# Main_4000_Model.net
KiCad netlist of a schematic drawn in EAGLE
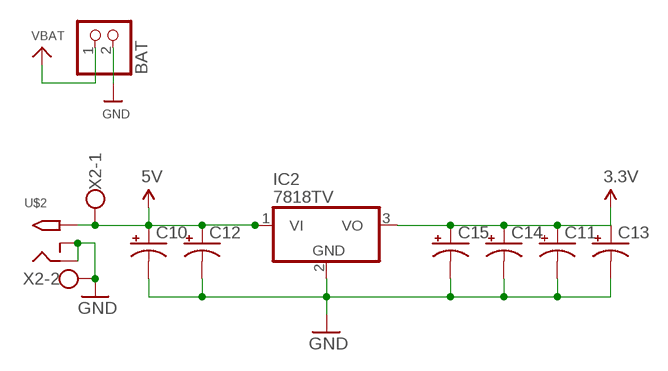
[diagram p0: schematic, sheet 1]
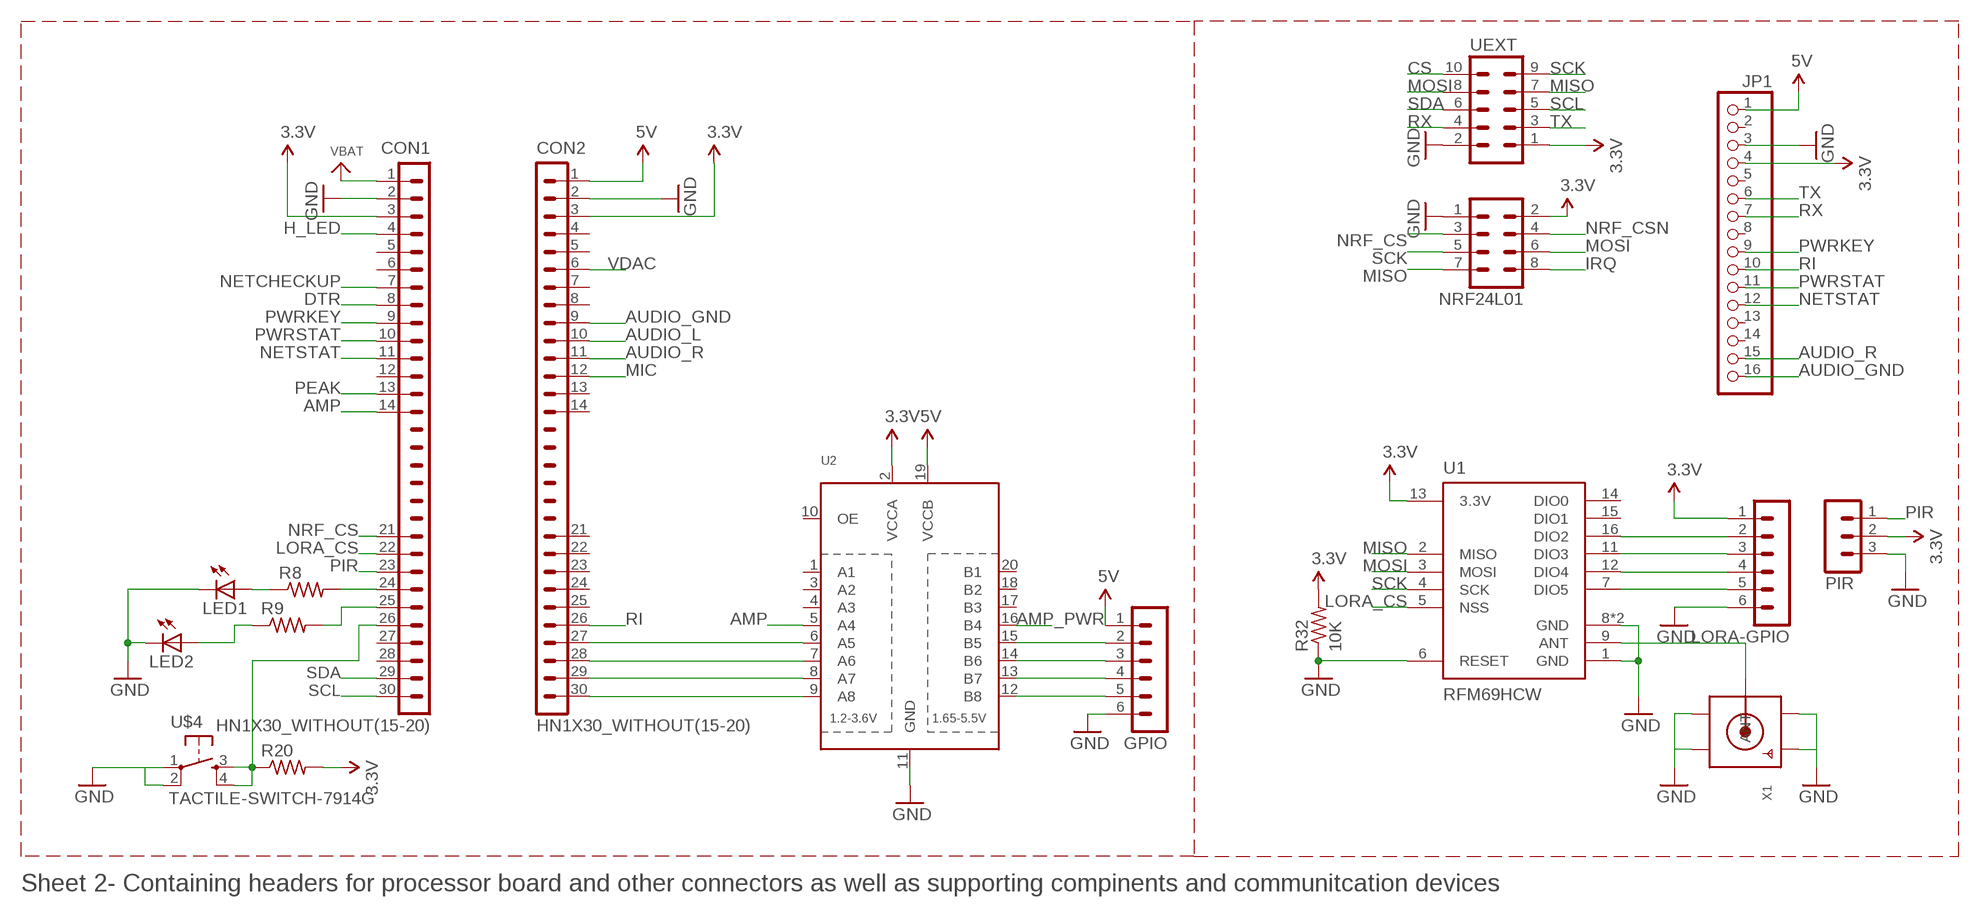
[diagram p1: schematic, sheet 2]
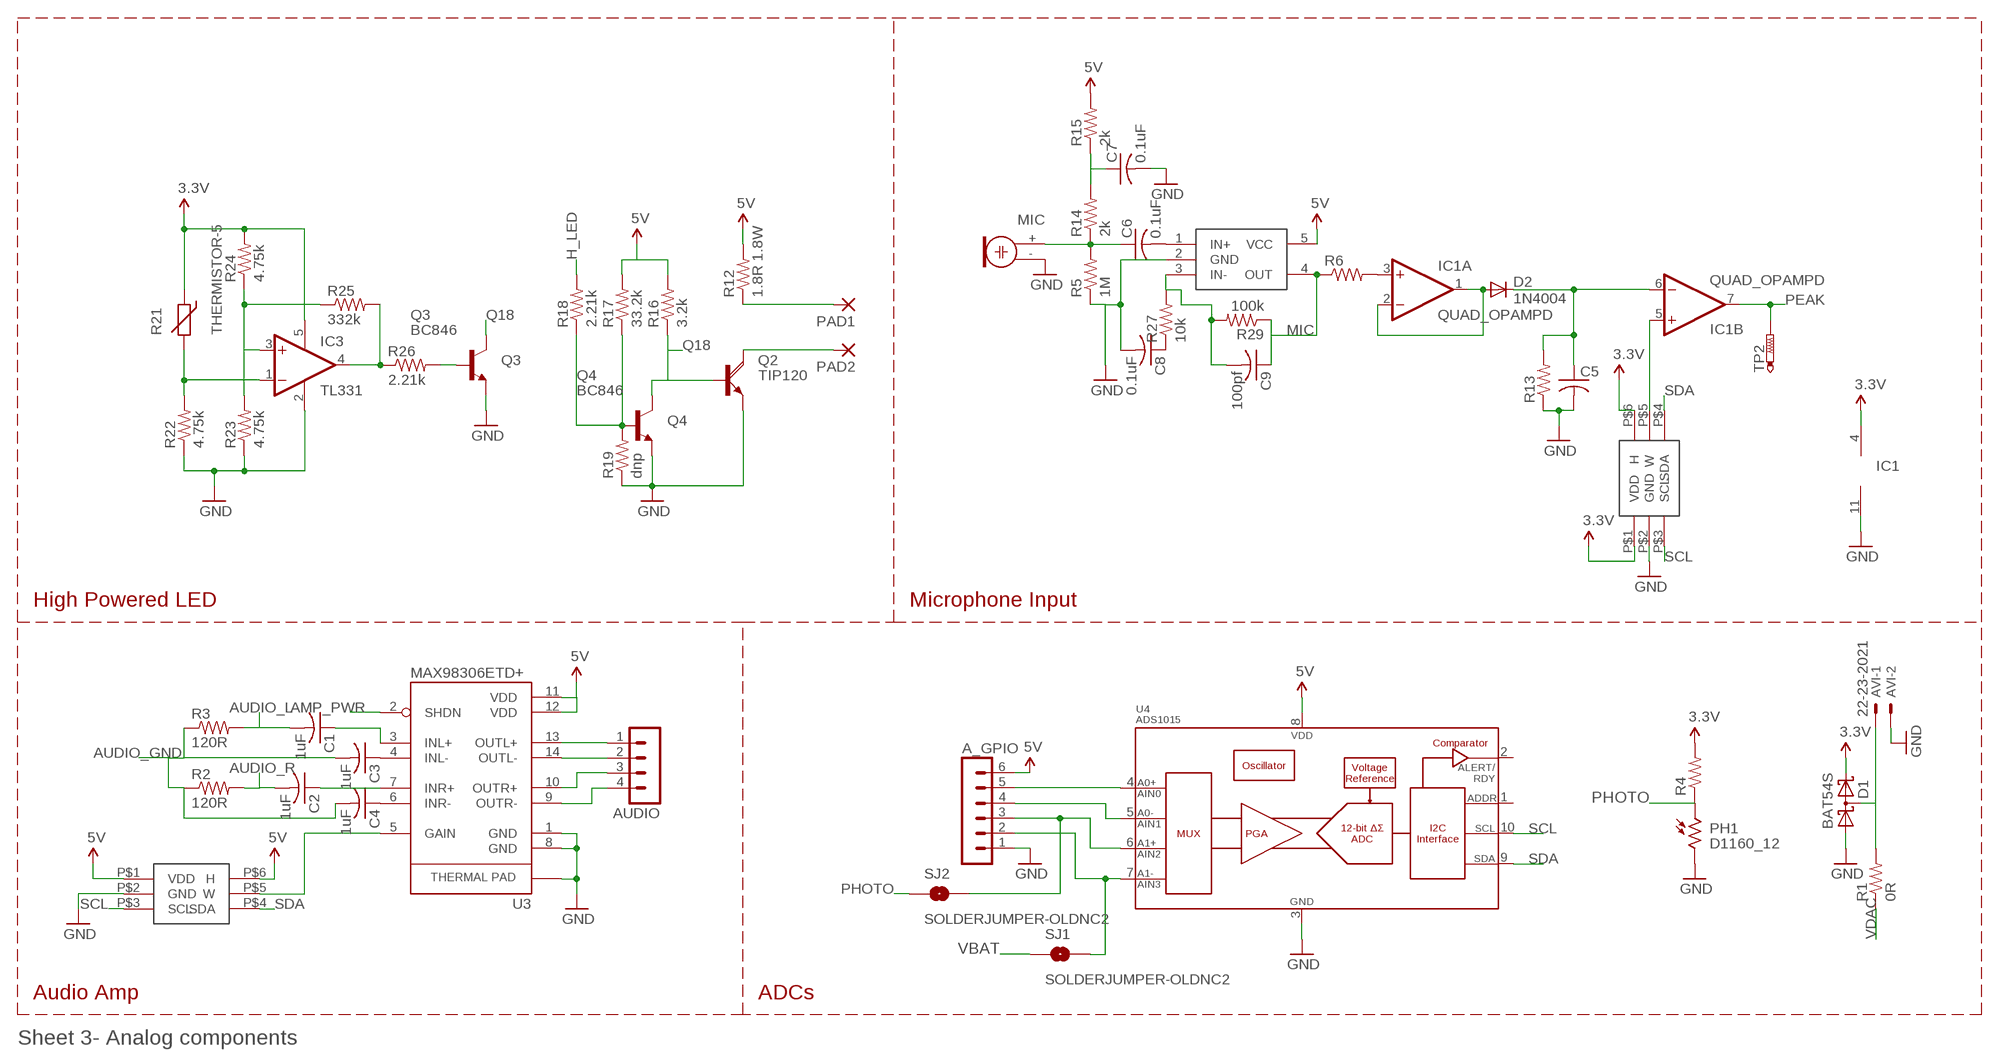
[diagram p2: schematic, sheet 3]
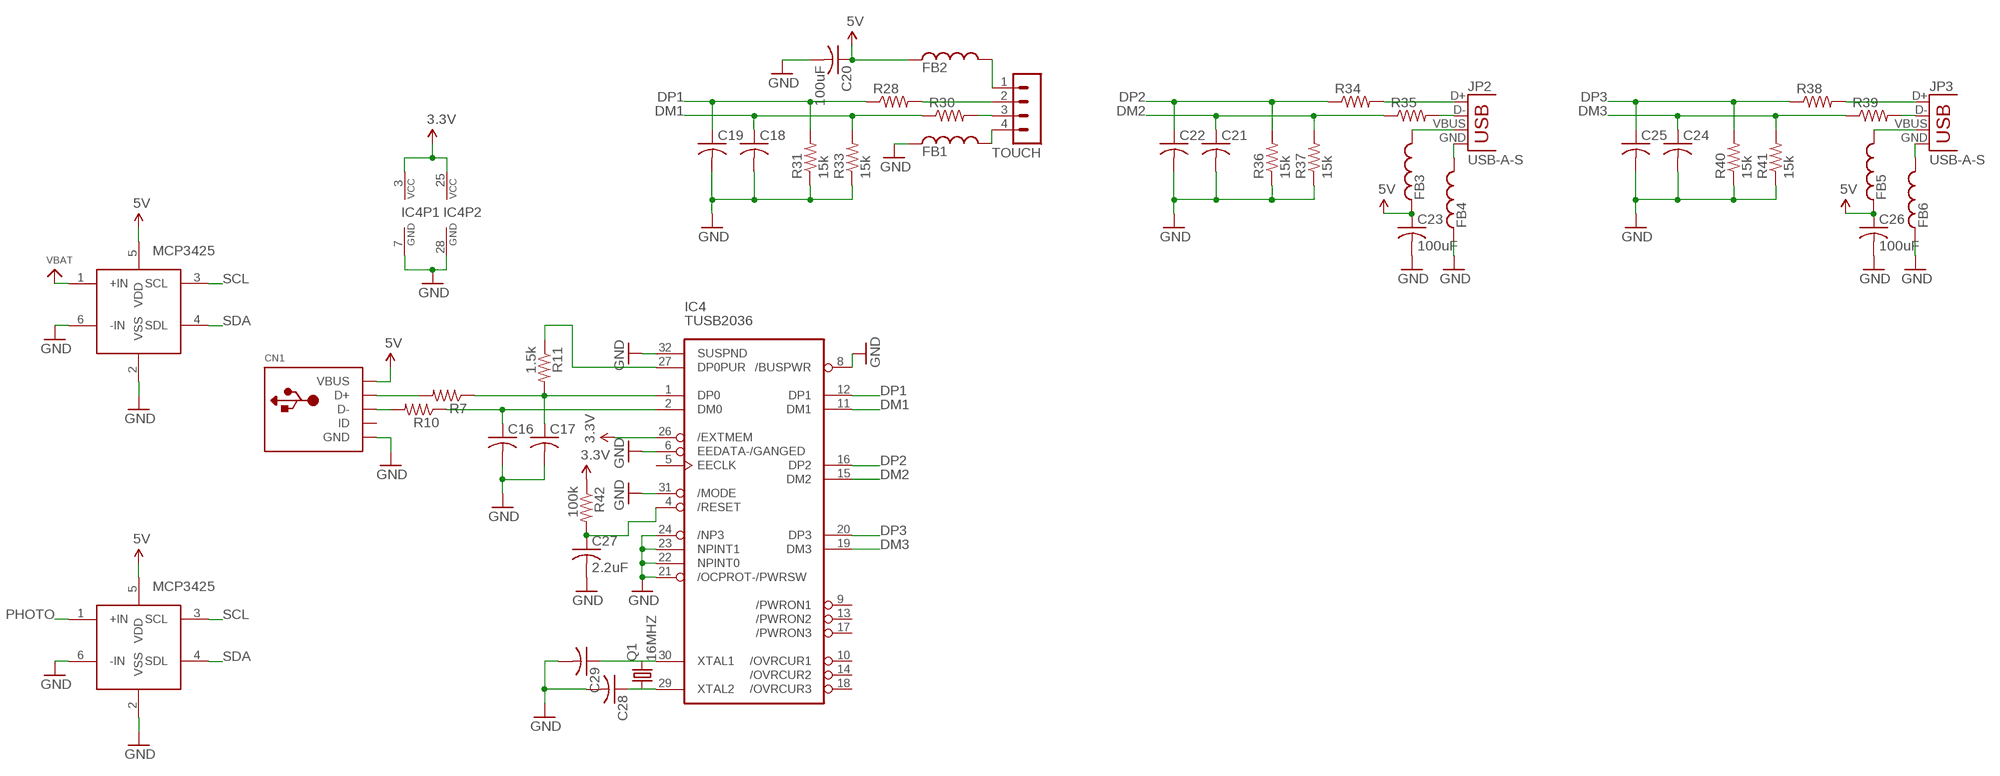
[diagram p3: schematic, sheet 4]

(export (version "E")
  (design (tool "Eeschema 10.0.6"))
  (components
    (comp (ref "CON1")
      (value "HN1X30_WITHOUT(15-20)")
      (footprint "eagle-import:HN1X30_WITHOUT(15-20)")
      (libsource (lib "eagle-import") (part "CON30_WITHOUT(15-20)"))
    )
    (comp (ref "CON2")
      (value "HN1X30_WITHOUT(15-20)")
      (footprint "eagle-import:HN1X30_WITHOUT(15-20)")
      (libsource (lib "eagle-import") (part "CON30_WITHOUT(15-20)"))
    )
    (comp (ref "GPIO")
      (value "MA06-1")
      (footprint "eagle-import:MA06-1")
      (libsource (lib "eagle-import") (part "MA06-1"))
    )
    (comp (ref "JP1")
      (value "PINHD-1X16")
      (footprint "eagle-import:1X16")
      (libsource (lib "eagle-import") (part "PINHD-1X16"))
    )
    (comp (ref "LED1")
      (value "LED5MM")
      (footprint "eagle-import:LED5MM")
      (libsource (lib "eagle-import") (part "LED5MM"))
    )
    (comp (ref "LED2")
      (value "LED5MM")
      (footprint "eagle-import:LED5MM")
      (libsource (lib "eagle-import") (part "LED5MM"))
    )
    (comp (ref "LORA-GPIO")
      (value "MA06-1")
      (footprint "eagle-import:MA06-1")
      (libsource (lib "eagle-import") (part "MA06-1"))
    )
    (comp (ref "NRF24L01")
      (value "MA04-2")
      (footprint "eagle-import:MA04-2")
      (libsource (lib "eagle-import") (part "MA04-2"))
    )
    (comp (ref "PIR")
      (value "MA03-1")
      (footprint "eagle-import:MA03-1")
      (libsource (lib "eagle-import") (part "MA03-1"))
    )
    (comp (ref "R8")
      (value "R-US_R0805")
      (footprint "eagle-import:R0805")
      (libsource (lib "eagle-import") (part "R-US_R0805"))
    )
    (comp (ref "R9")
      (value "R-US_R0805")
      (footprint "eagle-import:R0805")
      (libsource (lib "eagle-import") (part "R-US_R0805"))
    )
    (comp (ref "R20")
      (value "R-US_R0805")
      (footprint "eagle-import:R0805")
      (libsource (lib "eagle-import") (part "R-US_R0805"))
    )
    (comp (ref "R32")
      (value "10K")
      (footprint "eagle-import:R0805")
      (libsource (lib "eagle-import") (part "R-US_R0805"))
    )
    (comp (ref "U$4")
      (value "TACTILE-SWITCH-7914G")
      (footprint "eagle-import:7914G")
      (libsource (lib "eagle-import") (part "TACTILE-SWITCH-7914G"))
    )
    (comp (ref "U1")
      (value "RFM69HCW")
      (footprint "eagle-import:RFM69HCW-XXXS2")
      (libsource (lib "eagle-import") (part "RFM69HCW"))
    )
    (comp (ref "U2")
      (value "TXB0108PWR")
      (footprint "eagle-import:TSSOP20")
      (libsource (lib "eagle-import") (part "TXB0108PWR"))
    )
    (comp (ref "UEXT")
      (value "MA05-2")
      (footprint "eagle-import:MA05-2")
      (libsource (lib "eagle-import") (part "MA05-2"))
    )
    (comp (ref "X1")
      (value "SMACONNECTOR_EDGE")
      (footprint "eagle-import:SMA_EDGELAUNCH")
      (libsource (lib "eagle-import") (part "SMACONNECTOR_EDGE"))
    )
    (comp (ref "AUDIO")
      (value "MA04-1")
      (footprint "eagle-import:MA04-1")
      (libsource (lib "eagle-import") (part "MA04-1"))
    )
    (comp (ref "AVI")
      (value "22-23-2021")
      (footprint "eagle-import:22-23-2021")
      (fields (field (name "MF") "MOLEX"))
      (libsource (lib "eagle-import") (part "22-23-2021"))
    )
    (comp (ref "A_GPIO")
      (value "MA06-1")
      (footprint "eagle-import:MA06-1")
      (libsource (lib "eagle-import") (part "MA06-1"))
    )
    (comp (ref "C1")
      (value "1uF")
      (footprint "eagle-import:C0805")
      (libsource (lib "eagle-import") (part "C-USC0805"))
    )
    (comp (ref "C2")
      (value "1uF")
      (footprint "eagle-import:C0805")
      (libsource (lib "eagle-import") (part "C-USC0805"))
    )
    (comp (ref "C3")
      (value "1uF")
      (footprint "eagle-import:C0805")
      (libsource (lib "eagle-import") (part "C-USC0805"))
    )
    (comp (ref "C4")
      (value "1uF")
      (footprint "eagle-import:C0805")
      (libsource (lib "eagle-import") (part "C-USC0805"))
    )
    (comp (ref "C5")
      (value "C-USC0805K")
      (footprint "eagle-import:C0805K")
      (libsource (lib "eagle-import") (part "C-USC0805K"))
    )
    (comp (ref "C6")
      (value "0.1uF")
      (footprint "eagle-import:C0805")
      (libsource (lib "eagle-import") (part "C-USC0805"))
    )
    (comp (ref "C7")
      (value "0.1uF")
      (footprint "eagle-import:C0805")
      (libsource (lib "eagle-import") (part "C-USC0805"))
    )
    (comp (ref "C8")
      (value "0.1uF")
      (footprint "eagle-import:C0805")
      (libsource (lib "eagle-import") (part "C-USC0805"))
    )
    (comp (ref "C9")
      (value "100pf")
      (footprint "eagle-import:C0805")
      (libsource (lib "eagle-import") (part "C-USC0805"))
    )
    (comp (ref "D1")
      (value "BAT54S")
      (footprint "eagle-import:SOT23")
      (libsource (lib "eagle-import") (part "BAT54S"))
    )
    (comp (ref "D2")
      (value "1N4004")
      (footprint "eagle-import:DO41-10")
      (libsource (lib "eagle-import") (part "1N4004"))
    )
    (comp (ref "IC1")
      (value "QUAD_OPAMPD")
      (footprint "eagle-import:SO14")
      (libsource (lib "eagle-import") (part "QUAD_OPAMPD"))
    )
    (comp (ref "IC3")
      (value "TL331")
      (footprint "eagle-import:DBV-R-PDSO-G5")
      (libsource (lib "eagle-import") (part "TL331"))
    )
    (comp (ref "MIC")
      (value "ELECTRET")
      (footprint "eagle-import:9.7ELECTRET")
      (libsource (lib "eagle-import") (part "ELECTRET"))
    )
    (comp (ref "PAD1")
      (value "3,81/1,4")
      (footprint "eagle-import:3,81_1,4")
      (libsource (lib "eagle-import") (part "3,81/1,4"))
    )
    (comp (ref "PAD2")
      (value "3,81/1,4")
      (footprint "eagle-import:3,81_1,4")
      (libsource (lib "eagle-import") (part "3,81/1,4"))
    )
    (comp (ref "PH1")
      (value "D1160_12")
      (footprint "eagle-import:D11XX")
      (libsource (lib "eagle-import") (part "D1160_12"))
    )
    (comp (ref "Q2")
      (value "TIP120")
      (footprint "eagle-import:TO220AH")
      (libsource (lib "eagle-import") (part "TIP120"))
    )
    (comp (ref "Q3")
      (value "BC846")
      (footprint "eagle-import:SOT23")
      (libsource (lib "eagle-import") (part "BC846"))
    )
    (comp (ref "Q4")
      (value "BC846")
      (footprint "eagle-import:SOT23")
      (libsource (lib "eagle-import") (part "BC846"))
    )
    (comp (ref "R1")
      (value "0R")
      (footprint "eagle-import:R0805")
      (libsource (lib "eagle-import") (part "R-US_R0805"))
    )
    (comp (ref "R2")
      (value "120R")
      (footprint "eagle-import:R0805")
      (libsource (lib "eagle-import") (part "R-US_R0805"))
    )
    (comp (ref "R3")
      (value "120R")
      (footprint "eagle-import:R0805")
      (libsource (lib "eagle-import") (part "R-US_R0805"))
    )
    (comp (ref "R4")
      (value "R-US_R0805")
      (footprint "eagle-import:R0805")
      (libsource (lib "eagle-import") (part "R-US_R0805"))
    )
    (comp (ref "R5")
      (value "1M")
      (footprint "eagle-import:R0805")
      (libsource (lib "eagle-import") (part "R-US_R0805"))
    )
    (comp (ref "R6")
      (value "R-US_R0805")
      (footprint "eagle-import:R0805")
      (libsource (lib "eagle-import") (part "R-US_R0805"))
    )
    (comp (ref "R12")
      (value "1.8R 1.8W")
      (footprint "eagle-import:VMTB60")
      (libsource (lib "eagle-import") (part "R-US_VMTB60"))
    )
    (comp (ref "R13")
      (value "R-US_R0805")
      (footprint "eagle-import:R0805")
      (libsource (lib "eagle-import") (part "R-US_R0805"))
    )
    (comp (ref "R14")
      (value "2k")
      (footprint "eagle-import:R0805")
      (libsource (lib "eagle-import") (part "R-US_R0805"))
    )
    (comp (ref "R15")
      (value "2k")
      (footprint "eagle-import:R0805")
      (libsource (lib "eagle-import") (part "R-US_R0805"))
    )
    (comp (ref "R16")
      (value "3.2k")
      (footprint "eagle-import:R0805")
      (libsource (lib "eagle-import") (part "R-US_R0805"))
    )
    (comp (ref "R17")
      (value "33.2k")
      (footprint "eagle-import:R0805")
      (libsource (lib "eagle-import") (part "R-US_R0805"))
    )
    (comp (ref "R18")
      (value "2.21k")
      (footprint "eagle-import:R0805")
      (libsource (lib "eagle-import") (part "R-US_R0805"))
    )
    (comp (ref "R19")
      (value "dnp")
      (footprint "eagle-import:R0805")
      (libsource (lib "eagle-import") (part "R-US_R0805"))
    )
    (comp (ref "R21")
      (value "THERMISTOR-5")
      (footprint "eagle-import:R-5")
      (libsource (lib "eagle-import") (part "THERMISTOR-5"))
    )
    (comp (ref "R22")
      (value "4.75k")
      (footprint "eagle-import:R0805")
      (libsource (lib "eagle-import") (part "R-US_R0805"))
    )
    (comp (ref "R23")
      (value "4.75k")
      (footprint "eagle-import:R0805")
      (libsource (lib "eagle-import") (part "R-US_R0805"))
    )
    (comp (ref "R24")
      (value "4.75k")
      (footprint "eagle-import:R0805")
      (libsource (lib "eagle-import") (part "R-US_R0805"))
    )
    (comp (ref "R25")
      (value "332k")
      (footprint "eagle-import:R0805")
      (libsource (lib "eagle-import") (part "R-US_R0805"))
    )
    (comp (ref "R26")
      (value "2.21k")
      (footprint "eagle-import:R0805")
      (libsource (lib "eagle-import") (part "R-US_R0805"))
    )
    (comp (ref "R27")
      (value "10k")
      (footprint "eagle-import:R0805")
      (libsource (lib "eagle-import") (part "R-US_R0805"))
    )
    (comp (ref "R29")
      (value "100k")
      (footprint "eagle-import:R0805")
      (libsource (lib "eagle-import") (part "R-US_R0805"))
    )
    (comp (ref "SJ1")
      (value "SOLDERJUMPER-OLDNC2")
      (footprint "eagle-import:SJ_2S-NOTRACE")
      (libsource (lib "eagle-import") (part "SOLDERJUMPER-OLDNC2"))
    )
    (comp (ref "SJ2")
      (value "SOLDERJUMPER-OLDNC2")
      (footprint "eagle-import:SJ_2S-NOTRACE")
      (libsource (lib "eagle-import") (part "SOLDERJUMPER-OLDNC2"))
    )
    (comp (ref "TP2")
      (value "PTR1PAD1-13")
      (footprint "eagle-import:P1-13")
      (libsource (lib "eagle-import") (part "PTR1PAD1-13"))
    )
    (comp (ref "U$1")
      (value "TPL0401A/B")
      (footprint "eagle-import:SC-70")
      (libsource (lib "eagle-import") (part "TPL0401A/B"))
    )
    (comp (ref "U$3")
      (value "MAX4466")
      (footprint "eagle-import:SOT23-5L")
      (libsource (lib "eagle-import") (part "MAX4466"))
    )
    (comp (ref "U$5")
      (value "TPL0401A/B")
      (footprint "eagle-import:SC-70")
      (libsource (lib "eagle-import") (part "TPL0401A/B"))
    )
    (comp (ref "U3")
      (value "MAX98306ETD+")
      (footprint "eagle-import:14-TDFN")
      (libsource (lib "eagle-import") (part "MAX98306ETD+"))
    )
    (comp (ref "U4")
      (value "ADS1015")
      (footprint "eagle-import:MSOP10")
      (libsource (lib "eagle-import") (part "ADS1015"))
    )
    (comp (ref "C16")
      (value "C-USC0805")
      (footprint "eagle-import:C0805")
      (libsource (lib "eagle-import") (part "C-USC0805"))
    )
    (comp (ref "C17")
      (value "C-USC0805")
      (footprint "eagle-import:C0805")
      (libsource (lib "eagle-import") (part "C-USC0805"))
    )
    (comp (ref "C18")
      (value "C-USC0805")
      (footprint "eagle-import:C0805")
      (libsource (lib "eagle-import") (part "C-USC0805"))
    )
    (comp (ref "C19")
      (value "C-USC0805")
      (footprint "eagle-import:C0805")
      (libsource (lib "eagle-import") (part "C-USC0805"))
    )
    (comp (ref "C20")
      (value "100uF")
      (footprint "eagle-import:C0805")
      (libsource (lib "eagle-import") (part "C-USC0805"))
    )
    (comp (ref "C21")
      (value "C-USC0805")
      (footprint "eagle-import:C0805")
      (libsource (lib "eagle-import") (part "C-USC0805"))
    )
    (comp (ref "C22")
      (value "C-USC0805")
      (footprint "eagle-import:C0805")
      (libsource (lib "eagle-import") (part "C-USC0805"))
    )
    (comp (ref "C23")
      (value "100uF")
      (footprint "eagle-import:C0805")
      (libsource (lib "eagle-import") (part "C-USC0805"))
    )
    (comp (ref "C24")
      (value "C-USC0805")
      (footprint "eagle-import:C0805")
      (libsource (lib "eagle-import") (part "C-USC0805"))
    )
    (comp (ref "C25")
      (value "C-USC0805")
      (footprint "eagle-import:C0805")
      (libsource (lib "eagle-import") (part "C-USC0805"))
    )
    (comp (ref "C26")
      (value "100uF")
      (footprint "eagle-import:C0805")
      (libsource (lib "eagle-import") (part "C-USC0805"))
    )
    (comp (ref "C27")
      (value "2.2uF")
      (footprint "eagle-import:C0805")
      (libsource (lib "eagle-import") (part "C-USC0805"))
    )
    (comp (ref "C28")
      (value "C-USC0805")
      (footprint "eagle-import:C0805")
      (libsource (lib "eagle-import") (part "C-USC0805"))
    )
    (comp (ref "C29")
      (value "C-USC0805")
      (footprint "eagle-import:C0805")
      (libsource (lib "eagle-import") (part "C-USC0805"))
    )
    (comp (ref "CN1")
      (value "USBMOLEX")
      (footprint "eagle-import:USB-MINIB-THM-MOLEX")
      (libsource (lib "eagle-import") (part "USBMOLEX"))
    )
    (comp (ref "FB1")
      (value "FB1206")
      (footprint "eagle-import:FB1206")
      (libsource (lib "eagle-import") (part "FB1206"))
    )
    (comp (ref "FB2")
      (value "FB1206")
      (footprint "eagle-import:FB1206")
      (libsource (lib "eagle-import") (part "FB1206"))
    )
    (comp (ref "FB3")
      (value "FB1206")
      (footprint "eagle-import:FB1206")
      (libsource (lib "eagle-import") (part "FB1206"))
    )
    (comp (ref "FB4")
      (value "FB1206")
      (footprint "eagle-import:FB1206")
      (libsource (lib "eagle-import") (part "FB1206"))
    )
    (comp (ref "FB5")
      (value "FB1206")
      (footprint "eagle-import:FB1206")
      (libsource (lib "eagle-import") (part "FB1206"))
    )
    (comp (ref "FB6")
      (value "FB1206")
      (footprint "eagle-import:FB1206")
      (libsource (lib "eagle-import") (part "FB1206"))
    )
    (comp (ref "IC4")
      (value "TUSB2036")
      (footprint "eagle-import:LQFP32")
      (libsource (lib "eagle-import") (part "TUSB2036"))
    )
    (comp (ref "JP2")
      (value "USB-A-S")
      (footprint "eagle-import:USB-A-S")
      (libsource (lib "eagle-import") (part "USB-A-S"))
    )
    (comp (ref "JP3")
      (value "USB-A-S")
      (footprint "eagle-import:USB-A-S")
      (libsource (lib "eagle-import") (part "USB-A-S"))
    )
    (comp (ref "Q1")
      (value "16MHZ")
      (footprint "eagle-import:HC49UP")
      (libsource (lib "eagle-import") (part "CRYSTALHC49UP"))
    )
    (comp (ref "R7")
      (value "R-US_R0805")
      (footprint "eagle-import:R0805")
      (libsource (lib "eagle-import") (part "R-US_R0805"))
    )
    (comp (ref "R10")
      (value "R-US_R0805")
      (footprint "eagle-import:R0805")
      (libsource (lib "eagle-import") (part "R-US_R0805"))
    )
    (comp (ref "R11")
      (value "1.5k")
      (footprint "eagle-import:R0805")
      (libsource (lib "eagle-import") (part "R-US_R0805"))
    )
    (comp (ref "R28")
      (value "R-US_R0805")
      (footprint "eagle-import:R0805")
      (libsource (lib "eagle-import") (part "R-US_R0805"))
    )
    (comp (ref "R30")
      (value "R-US_R0805")
      (footprint "eagle-import:R0805")
      (libsource (lib "eagle-import") (part "R-US_R0805"))
    )
    (comp (ref "R31")
      (value "15k")
      (footprint "eagle-import:R0805")
      (libsource (lib "eagle-import") (part "R-US_R0805"))
    )
    (comp (ref "R33")
      (value "15k")
      (footprint "eagle-import:R0805")
      (libsource (lib "eagle-import") (part "R-US_R0805"))
    )
    (comp (ref "R34")
      (value "R-US_R0805")
      (footprint "eagle-import:R0805")
      (libsource (lib "eagle-import") (part "R-US_R0805"))
    )
    (comp (ref "R35")
      (value "R-US_R0805")
      (footprint "eagle-import:R0805")
      (libsource (lib "eagle-import") (part "R-US_R0805"))
    )
    (comp (ref "R36")
      (value "15k")
      (footprint "eagle-import:R0805")
      (libsource (lib "eagle-import") (part "R-US_R0805"))
    )
    (comp (ref "R37")
      (value "15k")
      (footprint "eagle-import:R0805")
      (libsource (lib "eagle-import") (part "R-US_R0805"))
    )
    (comp (ref "R38")
      (value "R-US_R0805")
      (footprint "eagle-import:R0805")
      (libsource (lib "eagle-import") (part "R-US_R0805"))
    )
    (comp (ref "R39")
      (value "R-US_R0805")
      (footprint "eagle-import:R0805")
      (libsource (lib "eagle-import") (part "R-US_R0805"))
    )
    (comp (ref "R40")
      (value "15k")
      (footprint "eagle-import:R0805")
      (libsource (lib "eagle-import") (part "R-US_R0805"))
    )
    (comp (ref "R41")
      (value "15k")
      (footprint "eagle-import:R0805")
      (libsource (lib "eagle-import") (part "R-US_R0805"))
    )
    (comp (ref "R42")
      (value "100k")
      (footprint "eagle-import:R0805")
      (libsource (lib "eagle-import") (part "R-US_R0805"))
    )
    (comp (ref "TOUCH")
      (value "MA04-1")
      (footprint "eagle-import:MA04-1")
      (libsource (lib "eagle-import") (part "MA04-1"))
    )
    (comp (ref "U$6")
      (value "MCP3425SOT")
      (footprint "eagle-import:SOT23-6")
      (libsource (lib "eagle-import") (part "MCP3425SOT"))
    )
    (comp (ref "U$8")
      (value "MCP3425SOT")
      (footprint "eagle-import:SOT23-6")
      (libsource (lib "eagle-import") (part "MCP3425SOT"))
    )
    (comp (ref "BAT")
      (value "JST_2PIN-SMT-RA")
      (footprint "eagle-import:JST-PH-2-SMT-RA")
      (libsource (lib "eagle-import") (part "JST_2PIN-SMT-RA"))
    )
    (comp (ref "C10")
      (value "CPOL-USE2.5-6")
      (footprint "eagle-import:E2,5-6")
      (libsource (lib "eagle-import") (part "CPOL-USE2.5-6"))
    )
    (comp (ref "C11")
      (value "CPOL-USE1.8-4")
      (footprint "eagle-import:E1,8-4")
      (libsource (lib "eagle-import") (part "CPOL-USE1.8-4"))
    )
    (comp (ref "C12")
      (value "CPOL-USE1.8-4")
      (footprint "eagle-import:E1,8-4")
      (libsource (lib "eagle-import") (part "CPOL-USE1.8-4"))
    )
    (comp (ref "C13")
      (value "CPOL-USE2.5-6")
      (footprint "eagle-import:E2,5-6")
      (libsource (lib "eagle-import") (part "CPOL-USE2.5-6"))
    )
    (comp (ref "C14")
      (value "CPOL-USE1.8-4")
      (footprint "eagle-import:E1,8-4")
      (libsource (lib "eagle-import") (part "CPOL-USE1.8-4"))
    )
    (comp (ref "C15")
      (value "CPOL-USE1.8-4")
      (footprint "eagle-import:E1,8-4")
      (libsource (lib "eagle-import") (part "CPOL-USE1.8-4"))
    )
    (comp (ref "IC2")
      (value "7818TV")
      (footprint "eagle-import:TO220V")
      (libsource (lib "eagle-import") (part "78TV18"))
    )
    (comp (ref "U$2")
      (value "2.1MMJACKTHM")
      (footprint "eagle-import:PJ-102A")
      (libsource (lib "eagle-import") (part "2.1MMJACKTHM"))
    )
    (comp (ref "X2")
      (value "W237-102")
      (footprint "eagle-import:W237-102")
      (fields (field (name "MPN") "237-102"))
      (libsource (lib "eagle-import") (part "W237-102"))
    )
  )
  (nets
    (net (code "1") (name "3.3V") (class "Default")
      (node (ref "C11") (pin "+") (pinfunction "+_+") (pintype "passive"))
      (node (ref "C13") (pin "+") (pinfunction "+_+") (pintype "passive"))
      (node (ref "C14") (pin "+") (pinfunction "+_+") (pintype "passive"))
      (node (ref "C15") (pin "+") (pinfunction "+_+") (pintype "passive"))
      (node (ref "CON1") (pin "3") (pinfunction "3_3") (pintype "passive"))
      (node (ref "CON2") (pin "3") (pinfunction "3_3") (pintype "passive"))
      (node (ref "D1") (pin "2") (pinfunction "C2_2") (pintype "passive"))
      (node (ref "IC1") (pin "4") (pinfunction "V+_4") (pintype "power_in"))
      (node (ref "IC2") (pin "3") (pinfunction "VO_3") (pintype "passive"))
      (node (ref "IC3") (pin "5") (pinfunction "V+_5") (pintype "power_in"))
      (node (ref "IC4") (pin "25") (pinfunction "VCC_25") (pintype "power_in"))
      (node (ref "IC4") (pin "26") (pinfunction "/EXTMEM_26") (pintype "input"))
      (node (ref "IC4") (pin "3") (pinfunction "VCC_3") (pintype "power_in"))
      (node (ref "JP1") (pin "4") (pinfunction "4_4") (pintype "passive"))
      (node (ref "LORA-GPIO") (pin "1") (pinfunction "1_1") (pintype "passive"))
      (node (ref "NRF24L01") (pin "2") (pinfunction "2_2") (pintype "passive"))
      (node (ref "PIR") (pin "2") (pinfunction "2_2") (pintype "passive"))
      (node (ref "R20") (pin "2") (pinfunction "2_2") (pintype "passive"))
      (node (ref "R21") (pin "1") (pinfunction "1_1") (pintype "passive"))
      (node (ref "R24") (pin "2") (pinfunction "2_2") (pintype "passive"))
      (node (ref "R32") (pin "2") (pinfunction "2_2") (pintype "passive"))
      (node (ref "R4") (pin "2") (pinfunction "2_2") (pintype "passive"))
      (node (ref "R42") (pin "1") (pinfunction "1_1") (pintype "passive"))
      (node (ref "U$5") (pin "P$1") (pinfunction "VDD_P$1") (pintype "bidirectional"))
      (node (ref "U$5") (pin "P$6") (pinfunction "H_P$6") (pintype "bidirectional"))
      (node (ref "U1") (pin "13") (pinfunction "3.3V_13") (pintype "power_in"))
      (node (ref "U2") (pin "2") (pinfunction "VCCA_2") (pintype "bidirectional"))
      (node (ref "UEXT") (pin "1") (pinfunction "1_1") (pintype "passive"))
    )
    (net (code "2") (name "5V") (class "Default")
      (node (ref "A_GPIO") (pin "6") (pinfunction "6_6") (pintype "passive"))
      (node (ref "C10") (pin "+") (pinfunction "+_+") (pintype "passive"))
      (node (ref "C12") (pin "+") (pinfunction "+_+") (pintype "passive"))
      (node (ref "C20") (pin "1") (pinfunction "1_1") (pintype "passive"))
      (node (ref "C23") (pin "1") (pinfunction "1_1") (pintype "passive"))
      (node (ref "C26") (pin "1") (pinfunction "1_1") (pintype "passive"))
      (node (ref "CN1") (pin "VBUS") (pinfunction "VBUS_VBUS") (pintype "power_in"))
      (node (ref "CON2") (pin "1") (pinfunction "1_1") (pintype "passive"))
      (node (ref "FB2") (pin "1") (pinfunction "1_1") (pintype "passive"))
      (node (ref "FB3") (pin "1") (pinfunction "1_1") (pintype "passive"))
      (node (ref "FB5") (pin "1") (pinfunction "1_1") (pintype "passive"))
      (node (ref "GPIO") (pin "1") (pinfunction "1_1") (pintype "passive"))
      (node (ref "IC2") (pin "1") (pinfunction "VI_1") (pintype "input"))
      (node (ref "JP1") (pin "1") (pinfunction "1_1") (pintype "passive"))
      (node (ref "R12") (pin "2") (pinfunction "2_2") (pintype "passive"))
      (node (ref "R15") (pin "2") (pinfunction "2_2") (pintype "passive"))
      (node (ref "R16") (pin "2") (pinfunction "2_2") (pintype "passive"))
      (node (ref "R17") (pin "2") (pinfunction "2_2") (pintype "passive"))
      (node (ref "U$1") (pin "P$1") (pinfunction "VDD_P$1") (pintype "bidirectional"))
      (node (ref "U$1") (pin "P$6") (pinfunction "H_P$6") (pintype "bidirectional"))
      (node (ref "U$2") (pin "TIP") (pinfunction "TIP_TIP") (pintype "bidirectional"))
      (node (ref "U$3") (pin "5") (pinfunction "VCC_5") (pintype "bidirectional"))
      (node (ref "U$6") (pin "5") (pinfunction "VDD_5") (pintype "bidirectional"))
      (node (ref "U$8") (pin "5") (pinfunction "VDD_5") (pintype "bidirectional"))
      (node (ref "U2") (pin "19") (pinfunction "VCCB_19") (pintype "bidirectional"))
      (node (ref "U3") (pin "11") (pinfunction "VDD_11") (pintype "power_in"))
      (node (ref "U3") (pin "12") (pinfunction "VDD_12") (pintype "power_in"))
      (node (ref "U4") (pin "8") (pinfunction "VDD_8") (pintype "bidirectional"))
      (node (ref "X2") (pin "1") (pinfunction "KL_1") (pintype "passive"))
    )
    (net (code "3") (name "AMP") (class "Default")
      (node (ref "CON1") (pin "14") (pinfunction "14_14") (pintype "passive"))
      (node (ref "U2") (pin "5") (pinfunction "A4_5") (pintype "bidirectional"))
    )
    (net (code "4") (name "AMP_PWR") (class "Default")
      (node (ref "U2") (pin "16") (pinfunction "B4_16") (pintype "bidirectional"))
      (node (ref "U3") (pin "2") (pinfunction "SHDN_2") (pintype "input"))
    )
    (net (code "5") (name "AUDIO_GND") (class "Default")
      (node (ref "C3") (pin "2") (pinfunction "2_2") (pintype "passive"))
      (node (ref "C4") (pin "2") (pinfunction "2_2") (pintype "passive"))
      (node (ref "CON2") (pin "9") (pinfunction "9_9") (pintype "passive"))
      (node (ref "JP1") (pin "16") (pinfunction "16_16") (pintype "passive"))
      (node (ref "R2") (pin "1") (pinfunction "1_1") (pintype "passive"))
      (node (ref "R3") (pin "1") (pinfunction "1_1") (pintype "passive"))
    )
    (net (code "6") (name "AUDIO_L") (class "Default")
      (node (ref "C1") (pin "2") (pinfunction "2_2") (pintype "passive"))
      (node (ref "CON2") (pin "10") (pinfunction "10_10") (pintype "passive"))
      (node (ref "R3") (pin "2") (pinfunction "2_2") (pintype "passive"))
    )
    (net (code "7") (name "AUDIO_R") (class "Default")
      (node (ref "C2") (pin "2") (pinfunction "2_2") (pintype "passive"))
      (node (ref "CON2") (pin "11") (pinfunction "11_11") (pintype "passive"))
      (node (ref "JP1") (pin "15") (pinfunction "15_15") (pintype "passive"))
      (node (ref "R2") (pin "2") (pinfunction "2_2") (pintype "passive"))
    )
    (net (code "8") (name "CS") (class "Default")
      (node (ref "UEXT") (pin "10") (pinfunction "10_10") (pintype "passive"))
    )
    (net (code "9") (name "DM1") (class "Default")
      (node (ref "C18") (pin "1") (pinfunction "1_1") (pintype "passive"))
      (node (ref "IC4") (pin "11") (pinfunction "DM1_11") (pintype "bidirectional"))
      (node (ref "R30") (pin "1") (pinfunction "1_1") (pintype "passive"))
      (node (ref "R33") (pin "2") (pinfunction "2_2") (pintype "passive"))
    )
    (net (code "10") (name "DM2") (class "Default")
      (node (ref "C21") (pin "1") (pinfunction "1_1") (pintype "passive"))
      (node (ref "IC4") (pin "15") (pinfunction "DM2_15") (pintype "bidirectional"))
      (node (ref "R35") (pin "1") (pinfunction "1_1") (pintype "passive"))
      (node (ref "R37") (pin "2") (pinfunction "2_2") (pintype "passive"))
    )
    (net (code "11") (name "DM3") (class "Default")
      (node (ref "C24") (pin "1") (pinfunction "1_1") (pintype "passive"))
      (node (ref "IC4") (pin "19") (pinfunction "DM3_19") (pintype "bidirectional"))
      (node (ref "R39") (pin "1") (pinfunction "1_1") (pintype "passive"))
      (node (ref "R41") (pin "2") (pinfunction "2_2") (pintype "passive"))
    )
    (net (code "12") (name "DP1") (class "Default")
      (node (ref "C19") (pin "1") (pinfunction "1_1") (pintype "passive"))
      (node (ref "IC4") (pin "12") (pinfunction "DP1_12") (pintype "bidirectional"))
      (node (ref "R28") (pin "1") (pinfunction "1_1") (pintype "passive"))
      (node (ref "R31") (pin "2") (pinfunction "2_2") (pintype "passive"))
    )
    (net (code "13") (name "DP2") (class "Default")
      (node (ref "C22") (pin "1") (pinfunction "1_1") (pintype "passive"))
      (node (ref "IC4") (pin "16") (pinfunction "DP2_16") (pintype "bidirectional"))
      (node (ref "R34") (pin "1") (pinfunction "1_1") (pintype "passive"))
      (node (ref "R36") (pin "2") (pinfunction "2_2") (pintype "passive"))
    )
    (net (code "14") (name "DP3") (class "Default")
      (node (ref "C25") (pin "1") (pinfunction "1_1") (pintype "passive"))
      (node (ref "IC4") (pin "20") (pinfunction "DP3_20") (pintype "bidirectional"))
      (node (ref "R38") (pin "1") (pinfunction "1_1") (pintype "passive"))
      (node (ref "R40") (pin "2") (pinfunction "2_2") (pintype "passive"))
    )
    (net (code "15") (name "DTR") (class "Default")
      (node (ref "CON1") (pin "8") (pinfunction "8_8") (pintype "passive"))
    )
    (net (code "16") (name "GND") (class "Default")
      (node (ref "AVI") (pin "2") (pinfunction "S_2") (pintype "passive"))
      (node (ref "A_GPIO") (pin "1") (pinfunction "1_1") (pintype "passive"))
      (node (ref "BAT") (pin "2") (pinfunction "1_2") (pintype "passive"))
      (node (ref "C10") (pin "-") (pinfunction "-_-") (pintype "passive"))
      (node (ref "C11") (pin "-") (pinfunction "-_-") (pintype "passive"))
      (node (ref "C12") (pin "-") (pinfunction "-_-") (pintype "passive"))
      (node (ref "C13") (pin "-") (pinfunction "-_-") (pintype "passive"))
      (node (ref "C14") (pin "-") (pinfunction "-_-") (pintype "passive"))
      (node (ref "C15") (pin "-") (pinfunction "-_-") (pintype "passive"))
      (node (ref "C16") (pin "2") (pinfunction "2_2") (pintype "passive"))
      (node (ref "C17") (pin "2") (pinfunction "2_2") (pintype "passive"))
      (node (ref "C18") (pin "2") (pinfunction "2_2") (pintype "passive"))
      (node (ref "C19") (pin "2") (pinfunction "2_2") (pintype "passive"))
      (node (ref "C20") (pin "2") (pinfunction "2_2") (pintype "passive"))
      (node (ref "C21") (pin "2") (pinfunction "2_2") (pintype "passive"))
      (node (ref "C22") (pin "2") (pinfunction "2_2") (pintype "passive"))
      (node (ref "C23") (pin "2") (pinfunction "2_2") (pintype "passive"))
      (node (ref "C24") (pin "2") (pinfunction "2_2") (pintype "passive"))
      (node (ref "C25") (pin "2") (pinfunction "2_2") (pintype "passive"))
      (node (ref "C26") (pin "2") (pinfunction "2_2") (pintype "passive"))
      (node (ref "C27") (pin "2") (pinfunction "2_2") (pintype "passive"))
      (node (ref "C28") (pin "2") (pinfunction "2_2") (pintype "passive"))
      (node (ref "C29") (pin "2") (pinfunction "2_2") (pintype "passive"))
      (node (ref "C5") (pin "2") (pinfunction "2_2") (pintype "passive"))
      (node (ref "C7") (pin "2") (pinfunction "2_2") (pintype "passive"))
      (node (ref "C8") (pin "2") (pinfunction "2_2") (pintype "passive"))
      (node (ref "CN1") (pin "GND") (pinfunction "GND_GND") (pintype "power_in"))
      (node (ref "CON1") (pin "2") (pinfunction "2_2") (pintype "passive"))
      (node (ref "CON2") (pin "2") (pinfunction "2_2") (pintype "passive"))
      (node (ref "D1") (pin "1") (pinfunction "A1_1") (pintype "passive"))
      (node (ref "FB1") (pin "1") (pinfunction "1_1") (pintype "passive"))
      (node (ref "FB4") (pin "1") (pinfunction "1_1") (pintype "passive"))
      (node (ref "FB6") (pin "1") (pinfunction "1_1") (pintype "passive"))
      (node (ref "GPIO") (pin "6") (pinfunction "6_6") (pintype "passive"))
      (node (ref "IC1") (pin "11") (pinfunction "V-_11") (pintype "power_in"))
      (node (ref "IC2") (pin "2") (pinfunction "GND_2") (pintype "passive"))
      (node (ref "IC3") (pin "2") (pinfunction "GND_2") (pintype "power_in"))
      (node (ref "IC4") (pin "21") (pinfunction "/OCPROT-/PWRSW_21") (pintype "input"))
      (node (ref "IC4") (pin "22") (pinfunction "NPINT0_22") (pintype "input"))
      (node (ref "IC4") (pin "23") (pinfunction "NPINT1_23") (pintype "input"))
      (node (ref "IC4") (pin "24") (pinfunction "/NP3_24") (pintype "input"))
      (node (ref "IC4") (pin "28") (pinfunction "GND_28") (pintype "power_in"))
      (node (ref "IC4") (pin "31") (pinfunction "/MODE_31") (pintype "input"))
      (node (ref "IC4") (pin "32") (pinfunction "SUSPND_32") (pintype "output"))
      (node (ref "IC4") (pin "6") (pinfunction "EEDATA-/GANGED_6") (pintype "bidirectional"))
      (node (ref "IC4") (pin "7") (pinfunction "GND_7") (pintype "power_in"))
      (node (ref "IC4") (pin "8") (pinfunction "/BUSPWR_8") (pintype "input"))
      (node (ref "JP1") (pin "3") (pinfunction "3_3") (pintype "passive"))
      (node (ref "LED1") (pin "K") (pinfunction "C_K") (pintype "passive"))
      (node (ref "LED2") (pin "K") (pinfunction "C_K") (pintype "passive"))
      (node (ref "LORA-GPIO") (pin "6") (pinfunction "6_6") (pintype "passive"))
      (node (ref "MIC") (pin "-") (pinfunction "1_-") (pintype "passive"))
      (node (ref "NRF24L01") (pin "1") (pinfunction "1_1") (pintype "passive"))
      (node (ref "PH1") (pin "2") (pinfunction "2_2") (pintype "passive"))
      (node (ref "PIR") (pin "3") (pinfunction "3_3") (pintype "passive"))
      (node (ref "Q2") (pin "E") (pinfunction "E_E") (pintype "passive"))
      (node (ref "Q3") (pin "2") (pinfunction "E_2") (pintype "passive"))
      (node (ref "Q4") (pin "2") (pinfunction "E_2") (pintype "passive"))
      (node (ref "R13") (pin "1") (pinfunction "1_1") (pintype "passive"))
      (node (ref "R19") (pin "1") (pinfunction "1_1") (pintype "passive"))
      (node (ref "R22") (pin "1") (pinfunction "1_1") (pintype "passive"))
      (node (ref "R23") (pin "1") (pinfunction "1_1") (pintype "passive"))
      (node (ref "R31") (pin "1") (pinfunction "1_1") (pintype "passive"))
      (node (ref "R32") (pin "1") (pinfunction "1_1") (pintype "passive"))
      (node (ref "R33") (pin "1") (pinfunction "1_1") (pintype "passive"))
      (node (ref "R36") (pin "1") (pinfunction "1_1") (pintype "passive"))
      (node (ref "R37") (pin "1") (pinfunction "1_1") (pintype "passive"))
      (node (ref "R40") (pin "1") (pinfunction "1_1") (pintype "passive"))
      (node (ref "R41") (pin "1") (pinfunction "1_1") (pintype "passive"))
      (node (ref "R5") (pin "1") (pinfunction "1_1") (pintype "passive"))
      (node (ref "U$1") (pin "P$2") (pinfunction "GND_P$2") (pintype "bidirectional"))
      (node (ref "U$2") (pin "RING") (pinfunction "RING_RING") (pintype "bidirectional"))
      (node (ref "U$2") (pin "RING_SW") (pinfunction "RING_SW_RING_SW") (pintype "bidirectional"))
      (node (ref "U$3") (pin "2") (pinfunction "GND_2") (pintype "bidirectional"))
      (node (ref "U$4") (pin "1") (pinfunction "1_1") (pintype "passive"))
      (node (ref "U$4") (pin "2") (pinfunction "2_2") (pintype "passive"))
      (node (ref "U$5") (pin "P$2") (pinfunction "GND_P$2") (pintype "bidirectional"))
      (node (ref "U$6") (pin "2") (pinfunction "VSS_2") (pintype "bidirectional"))
      (node (ref "U$6") (pin "6") (pinfunction "-IN_6") (pintype "bidirectional"))
      (node (ref "U$8") (pin "2") (pinfunction "VSS_2") (pintype "bidirectional"))
      (node (ref "U$8") (pin "6") (pinfunction "-IN_6") (pintype "bidirectional"))
      (node (ref "U1") (pin "1") (pinfunction "GND_1") (pintype "power_in"))
      (node (ref "U1") (pin "10") (pinfunction "GND_10") (pintype "power_in"))
      (node (ref "U1") (pin "6") (pinfunction "RESET_6") (pintype "input"))
      (node (ref "U1") (pin "8") (pinfunction "GND_8") (pintype "power_in"))
      (node (ref "U2") (pin "11") (pinfunction "GND_11") (pintype "bidirectional"))
      (node (ref "U3") (pin "1") (pinfunction "GND_1") (pintype "power_in"))
      (node (ref "U3") (pin "15") (pinfunction "GND_15") (pintype "power_in"))
      (node (ref "U3") (pin "8") (pinfunction "GND_8") (pintype "power_in"))
      (node (ref "U4") (pin "3") (pinfunction "VSS_3") (pintype "bidirectional"))
      (node (ref "UEXT") (pin "2") (pinfunction "2_2") (pintype "passive"))
      (node (ref "X1") (pin "GND@1") (pinfunction "GND4_GND@1") (pintype "power_in"))
      (node (ref "X1") (pin "GND@2") (pinfunction "GND3_GND@2") (pintype "power_in"))
      (node (ref "X1") (pin "GND@3") (pinfunction "GND2_GND@3") (pintype "power_in"))
      (node (ref "X1") (pin "GND@4") (pinfunction "GND1_GND@4") (pintype "power_in"))
      (node (ref "X2") (pin "2") (pinfunction "KL_2") (pintype "passive"))
    )
    (net (code "17") (name "H_LED") (class "Default")
      (node (ref "CON1") (pin "4") (pinfunction "4_4") (pintype "passive"))
      (node (ref "R18") (pin "2") (pinfunction "2_2") (pintype "passive"))
    )
    (net (code "18") (name "IRQ") (class "Default")
      (node (ref "NRF24L01") (pin "8") (pinfunction "8_8") (pintype "passive"))
    )
    (net (code "19") (name "LORA_CS") (class "Default")
      (node (ref "CON1") (pin "22") (pinfunction "22_22") (pintype "passive"))
      (node (ref "U1") (pin "5") (pinfunction "NSS_5") (pintype "input"))
    )
    (net (code "20") (name "MIC") (class "Default")
      (node (ref "C9") (pin "1") (pinfunction "1_1") (pintype "passive"))
      (node (ref "CON2") (pin "12") (pinfunction "12_12") (pintype "passive"))
      (node (ref "R29") (pin "1") (pinfunction "1_1") (pintype "passive"))
      (node (ref "R6") (pin "1") (pinfunction "1_1") (pintype "passive"))
      (node (ref "U$3") (pin "4") (pinfunction "OUT_4") (pintype "bidirectional"))
    )
    (net (code "21") (name "MISO") (class "Default")
      (node (ref "NRF24L01") (pin "7") (pinfunction "7_7") (pintype "passive"))
      (node (ref "U1") (pin "2") (pinfunction "MISO_2") (pintype "bidirectional"))
      (node (ref "UEXT") (pin "7") (pinfunction "7_7") (pintype "passive"))
    )
    (net (code "22") (name "MOSI") (class "Default")
      (node (ref "NRF24L01") (pin "6") (pinfunction "6_6") (pintype "passive"))
      (node (ref "U1") (pin "3") (pinfunction "MOSI_3") (pintype "input"))
      (node (ref "UEXT") (pin "8") (pinfunction "8_8") (pintype "passive"))
    )
    (net (code "23") (name "NETCHECKUP") (class "Default")
      (node (ref "CON1") (pin "7") (pinfunction "7_7") (pintype "passive"))
    )
    (net (code "24") (name "NETSTAT") (class "Default")
      (node (ref "CON1") (pin "11") (pinfunction "11_11") (pintype "passive"))
      (node (ref "JP1") (pin "12") (pinfunction "12_12") (pintype "passive"))
    )
    (net (code "25") (name "NRF_CS") (class "Default")
      (node (ref "CON1") (pin "21") (pinfunction "21_21") (pintype "passive"))
      (node (ref "NRF24L01") (pin "3") (pinfunction "3_3") (pintype "passive"))
    )
    (net (code "26") (name "NRF_CSN") (class "Default")
      (node (ref "NRF24L01") (pin "4") (pinfunction "4_4") (pintype "passive"))
    )
    (net (code "27") (name "Net-(AVIA-S)") (class "Default")
      (node (ref "AVI") (pin "1") (pinfunction "S_1") (pintype "passive"))
      (node (ref "D1") (pin "3") (pinfunction "C1A2_3") (pintype "passive"))
      (node (ref "R1") (pin "2") (pinfunction "2_2") (pintype "passive"))
    )
    (net (code "28") (name "Net-(C7-Pad1)") (class "Default")
      (node (ref "C7") (pin "1") (pinfunction "1_1") (pintype "passive"))
      (node (ref "R14") (pin "2") (pinfunction "2_2") (pintype "passive"))
      (node (ref "R15") (pin "1") (pinfunction "1_1") (pintype "passive"))
    )
    (net (code "29") (name "Net-(C8-Pad1)") (class "Default")
      (node (ref "C8") (pin "1") (pinfunction "1_1") (pintype "passive"))
      (node (ref "R27") (pin "1") (pinfunction "1_1") (pintype "passive"))
    )
    (net (code "30") (name "Net-(CN1-PadD+)") (class "Default")
      (node (ref "CN1") (pin "D+") (pinfunction "D+_D+") (pintype "bidirectional"))
      (node (ref "R7") (pin "2") (pinfunction "2_2") (pintype "passive"))
    )
    (net (code "31") (name "Net-(CN1-PadD-)") (class "Default")
      (node (ref "CN1") (pin "D-") (pinfunction "D-_D-") (pintype "bidirectional"))
      (node (ref "R10") (pin "2") (pinfunction "2_2") (pintype "passive"))
    )
    (net (code "32") (name "Net-(CON1-Pad24)") (class "Default")
      (node (ref "CON1") (pin "24") (pinfunction "24_24") (pintype "passive"))
      (node (ref "R8") (pin "2") (pinfunction "2_2") (pintype "passive"))
    )
    (net (code "33") (name "Net-(CON1-Pad25)") (class "Default")
      (node (ref "CON1") (pin "25") (pinfunction "25_25") (pintype "passive"))
      (node (ref "R9") (pin "2") (pinfunction "2_2") (pintype "passive"))
    )
    (net (code "34") (name "Net-(CON1-Pad26)") (class "Default")
      (node (ref "CON1") (pin "26") (pinfunction "26_26") (pintype "passive"))
      (node (ref "R20") (pin "1") (pinfunction "1_1") (pintype "passive"))
      (node (ref "U$4") (pin "3") (pinfunction "3_3") (pintype "passive"))
      (node (ref "U$4") (pin "4") (pinfunction "4_4") (pintype "passive"))
    )
    (net (code "35") (name "Net-(FB1-Pad2)") (class "Default")
      (node (ref "FB1") (pin "2") (pinfunction "2_2") (pintype "passive"))
      (node (ref "TOUCH") (pin "4") (pinfunction "4_4") (pintype "passive"))
    )
    (net (code "36") (name "Net-(FB2-Pad2)") (class "Default")
      (node (ref "FB2") (pin "2") (pinfunction "2_2") (pintype "passive"))
      (node (ref "TOUCH") (pin "1") (pinfunction "1_1") (pintype "passive"))
    )
    (net (code "37") (name "Net-(FB3-Pad2)") (class "Default")
      (node (ref "FB3") (pin "2") (pinfunction "2_2") (pintype "passive"))
      (node (ref "JP2") (pin "VBUS") (pinfunction "VBUS_VBUS") (pintype "bidirectional"))
    )
    (net (code "38") (name "Net-(FB4-Pad2)") (class "Default")
      (node (ref "FB4") (pin "2") (pinfunction "2_2") (pintype "passive"))
      (node (ref "JP2") (pin "GND") (pinfunction "GND_GND") (pintype "bidirectional"))
    )
    (net (code "39") (name "Net-(FB5-Pad2)") (class "Default")
      (node (ref "FB5") (pin "2") (pinfunction "2_2") (pintype "passive"))
      (node (ref "JP3") (pin "VBUS") (pinfunction "VBUS_VBUS") (pintype "bidirectional"))
    )
    (net (code "40") (name "Net-(FB6-Pad2)") (class "Default")
      (node (ref "FB6") (pin "2") (pinfunction "2_2") (pintype "passive"))
      (node (ref "JP3") (pin "GND") (pinfunction "GND_GND") (pintype "bidirectional"))
    )
    (net (code "41") (name "Net-(IC1A-+IN)") (class "Default")
      (node (ref "IC1") (pin "3") (pinfunction "+IN_3") (pintype "input"))
      (node (ref "R6") (pin "2") (pinfunction "2_2") (pintype "passive"))
    )
    (net (code "42") (name "Net-(IC1A--IN)") (class "Default")
      (node (ref "D2") (pin "A") (pinfunction "A_A") (pintype "passive"))
      (node (ref "IC1") (pin "1") (pinfunction "OUT_1") (pintype "output"))
      (node (ref "IC1") (pin "2") (pinfunction "-IN_2") (pintype "input"))
    )
    (net (code "43") (name "Net-(IC1B-+IN)") (class "Default")
      (node (ref "IC1") (pin "5") (pinfunction "+IN_5") (pintype "input"))
      (node (ref "U$5") (pin "P$5") (pinfunction "W_P$5") (pintype "bidirectional"))
    )
    (net (code "44") (name "Net-(IC1B--IN)") (class "Default")
      (node (ref "C5") (pin "1") (pinfunction "1_1") (pintype "passive"))
      (node (ref "D2") (pin "C") (pinfunction "C_C") (pintype "passive"))
      (node (ref "IC1") (pin "6") (pinfunction "-IN_6") (pintype "input"))
      (node (ref "R13") (pin "2") (pinfunction "2_2") (pintype "passive"))
    )
    (net (code "45") (name "Net-(IC3-+IN)") (class "Default")
      (node (ref "IC3") (pin "3") (pinfunction "+IN_3") (pintype "input"))
      (node (ref "R23") (pin "2") (pinfunction "2_2") (pintype "passive"))
      (node (ref "R24") (pin "1") (pinfunction "1_1") (pintype "passive"))
      (node (ref "R25") (pin "1") (pinfunction "1_1") (pintype "passive"))
    )
    (net (code "46") (name "Net-(IC3--IN)") (class "Default")
      (node (ref "IC3") (pin "1") (pinfunction "-IN_1") (pintype "input"))
      (node (ref "R21") (pin "2") (pinfunction "2_2") (pintype "passive"))
      (node (ref "R22") (pin "2") (pinfunction "2_2") (pintype "passive"))
    )
    (net (code "47") (name "Net-(IC3-OUT)") (class "Default")
      (node (ref "IC3") (pin "4") (pinfunction "OUT_4") (pintype "output"))
      (node (ref "R25") (pin "2") (pinfunction "2_2") (pintype "passive"))
      (node (ref "R26") (pin "1") (pinfunction "1_1") (pintype "passive"))
    )
    (net (code "48") (name "Net-(IC4A-DM0)") (class "Default")
      (node (ref "C16") (pin "1") (pinfunction "1_1") (pintype "passive"))
      (node (ref "IC4") (pin "2") (pinfunction "DM0_2") (pintype "bidirectional"))
      (node (ref "R10") (pin "1") (pinfunction "1_1") (pintype "passive"))
    )
    (net (code "49") (name "Net-(IC4A-DP0)") (class "Default")
      (node (ref "C17") (pin "1") (pinfunction "1_1") (pintype "passive"))
      (node (ref "IC4") (pin "1") (pinfunction "DP0_1") (pintype "bidirectional"))
      (node (ref "R11") (pin "2") (pinfunction "2_2") (pintype "passive"))
      (node (ref "R7") (pin "1") (pinfunction "1_1") (pintype "passive"))
    )
    (net (code "50") (name "Net-(IC4A-DP0PUR)") (class "Default")
      (node (ref "IC4") (pin "27") (pinfunction "DP0PUR_27") (pintype "output"))
      (node (ref "R11") (pin "1") (pinfunction "1_1") (pintype "passive"))
    )
    (net (code "51") (name "Net-(IC4A-XTAL1)") (class "Default")
      (node (ref "C29") (pin "1") (pinfunction "1_1") (pintype "passive"))
      (node (ref "IC4") (pin "30") (pinfunction "XTAL1_30") (pintype "input"))
      (node (ref "Q1") (pin "2") (pinfunction "2_2") (pintype "passive"))
    )
    (net (code "52") (name "Net-(IC4A-XTAL2)") (class "Default")
      (node (ref "C28") (pin "1") (pinfunction "1_1") (pintype "passive"))
      (node (ref "IC4") (pin "29") (pinfunction "XTAL2_29") (pintype "output"))
      (node (ref "Q1") (pin "1") (pinfunction "1_1") (pintype "passive"))
    )
    (net (code "53") (name "Net-(IC4A-{slash}RESET)") (class "Default")
      (node (ref "C27") (pin "1") (pinfunction "1_1") (pintype "passive"))
      (node (ref "IC4") (pin "4") (pinfunction "/RESET_4") (pintype "input"))
      (node (ref "R42") (pin "2") (pinfunction "2_2") (pintype "passive"))
    )
    (net (code "54") (name "Net-(JP2-PadD+)") (class "Default")
      (node (ref "JP2") (pin "D+") (pinfunction "D+_D+") (pintype "bidirectional"))
      (node (ref "R34") (pin "2") (pinfunction "2_2") (pintype "passive"))
    )
    (net (code "55") (name "Net-(JP2-PadD-)") (class "Default")
      (node (ref "JP2") (pin "D-") (pinfunction "D-_D-") (pintype "bidirectional"))
      (node (ref "R35") (pin "2") (pinfunction "2_2") (pintype "passive"))
    )
    (net (code "56") (name "Net-(JP3-PadD+)") (class "Default")
      (node (ref "JP3") (pin "D+") (pinfunction "D+_D+") (pintype "bidirectional"))
      (node (ref "R38") (pin "2") (pinfunction "2_2") (pintype "passive"))
    )
    (net (code "57") (name "Net-(JP3-PadD-)") (class "Default")
      (node (ref "JP3") (pin "D-") (pinfunction "D-_D-") (pintype "bidirectional"))
      (node (ref "R39") (pin "2") (pinfunction "2_2") (pintype "passive"))
    )
    (net (code "58") (name "Net-(LED1-PadA)") (class "Default")
      (node (ref "LED1") (pin "A") (pinfunction "A_A") (pintype "passive"))
      (node (ref "R8") (pin "1") (pinfunction "1_1") (pintype "passive"))
    )
    (net (code "59") (name "Net-(LED2-PadA)") (class "Default")
      (node (ref "LED2") (pin "A") (pinfunction "A_A") (pintype "passive"))
      (node (ref "R9") (pin "1") (pinfunction "1_1") (pintype "passive"))
    )
    (net (code "60") (name "Net-(MIC-2)") (class "Default")
      (node (ref "C6") (pin "1") (pinfunction "1_1") (pintype "passive"))
      (node (ref "MIC") (pin "+") (pinfunction "2_+") (pintype "passive"))
      (node (ref "R14") (pin "1") (pinfunction "1_1") (pintype "passive"))
      (node (ref "R5") (pin "2") (pinfunction "2_2") (pintype "passive"))
    )
    (net (code "61") (name "Net-(PAD1-P)") (class "Default")
      (node (ref "PAD1") (pin "1") (pinfunction "P_1") (pintype "passive"))
      (node (ref "R12") (pin "1") (pinfunction "1_1") (pintype "passive"))
    )
    (net (code "62") (name "Net-(PAD2-P)") (class "Default")
      (node (ref "PAD2") (pin "1") (pinfunction "P_1") (pintype "passive"))
      (node (ref "Q2") (pin "C") (pinfunction "C_C") (pintype "passive"))
    )
    (net (code "63") (name "Net-(Q3-B)") (class "Default")
      (node (ref "Q3") (pin "1") (pinfunction "B_1") (pintype "passive"))
      (node (ref "R26") (pin "2") (pinfunction "2_2") (pintype "passive"))
    )
    (net (code "64") (name "Net-(Q4-B)") (class "Default")
      (node (ref "Q4") (pin "1") (pinfunction "B_1") (pintype "passive"))
      (node (ref "R17") (pin "1") (pinfunction "1_1") (pintype "passive"))
      (node (ref "R18") (pin "1") (pinfunction "1_1") (pintype "passive"))
      (node (ref "R19") (pin "2") (pinfunction "2_2") (pintype "passive"))
    )
    (net (code "65") (name "Net-(R28-Pad2)") (class "Default")
      (node (ref "R28") (pin "2") (pinfunction "2_2") (pintype "passive"))
      (node (ref "TOUCH") (pin "2") (pinfunction "2_2") (pintype "passive"))
    )
    (net (code "66") (name "Net-(R30-Pad2)") (class "Default")
      (node (ref "R30") (pin "2") (pinfunction "2_2") (pintype "passive"))
      (node (ref "TOUCH") (pin "3") (pinfunction "3_3") (pintype "passive"))
    )
    (net (code "67") (name "Net-(U$1-W)") (class "Default")
      (node (ref "U$1") (pin "P$5") (pinfunction "W_P$5") (pintype "bidirectional"))
      (node (ref "U3") (pin "5") (pinfunction "GAIN_5") (pintype "passive"))
    )
    (net (code "68") (name "Net-(U$3-IN+)") (class "Default")
      (node (ref "C6") (pin "2") (pinfunction "2_2") (pintype "passive"))
      (node (ref "U$3") (pin "1") (pinfunction "IN+_1") (pintype "bidirectional"))
    )
    (net (code "69") (name "Net-(U$3-IN-)") (class "Default")
      (node (ref "C9") (pin "2") (pinfunction "2_2") (pintype "passive"))
      (node (ref "R27") (pin "2") (pinfunction "2_2") (pintype "passive"))
      (node (ref "R29") (pin "2") (pinfunction "2_2") (pintype "passive"))
      (node (ref "U$3") (pin "3") (pinfunction "IN-_3") (pintype "bidirectional"))
    )
    (net (code "70") (name "Net-(U1-ANT)") (class "Default")
      (node (ref "U1") (pin "9") (pinfunction "ANT_9") (pintype "passive"))
      (node (ref "X1") (pin "P") (pinfunction "ANT_P") (pintype "bidirectional"))
    )
    (net (code "71") (name "Net-(U1-DIO2)") (class "Default")
      (node (ref "LORA-GPIO") (pin "2") (pinfunction "2_2") (pintype "passive"))
      (node (ref "U1") (pin "16") (pinfunction "DIO2_16") (pintype "bidirectional"))
    )
    (net (code "72") (name "Net-(U1-DIO3)") (class "Default")
      (node (ref "LORA-GPIO") (pin "3") (pinfunction "3_3") (pintype "passive"))
      (node (ref "U1") (pin "11") (pinfunction "DIO3_11") (pintype "bidirectional"))
    )
    (net (code "73") (name "Net-(U1-DIO4)") (class "Default")
      (node (ref "LORA-GPIO") (pin "4") (pinfunction "4_4") (pintype "passive"))
      (node (ref "U1") (pin "12") (pinfunction "DIO4_12") (pintype "bidirectional"))
    )
    (net (code "74") (name "Net-(U1-DIO5)") (class "Default")
      (node (ref "LORA-GPIO") (pin "5") (pinfunction "5_5") (pintype "passive"))
      (node (ref "U1") (pin "7") (pinfunction "DIO5_7") (pintype "bidirectional"))
    )
    (net (code "75") (name "Net-(U2-A5)") (class "Default")
      (node (ref "CON2") (pin "27") (pinfunction "27_27") (pintype "passive"))
      (node (ref "U2") (pin "6") (pinfunction "A5_6") (pintype "bidirectional"))
    )
    (net (code "76") (name "Net-(U2-A6)") (class "Default")
      (node (ref "CON2") (pin "28") (pinfunction "28_28") (pintype "passive"))
      (node (ref "U2") (pin "7") (pinfunction "A6_7") (pintype "bidirectional"))
    )
    (net (code "77") (name "Net-(U2-A7)") (class "Default")
      (node (ref "CON2") (pin "29") (pinfunction "29_29") (pintype "passive"))
      (node (ref "U2") (pin "8") (pinfunction "A7_8") (pintype "bidirectional"))
    )
    (net (code "78") (name "Net-(U2-A8)") (class "Default")
      (node (ref "CON2") (pin "30") (pinfunction "30_30") (pintype "passive"))
      (node (ref "U2") (pin "9") (pinfunction "A8_9") (pintype "bidirectional"))
    )
    (net (code "79") (name "Net-(U2-B5)") (class "Default")
      (node (ref "GPIO") (pin "2") (pinfunction "2_2") (pintype "passive"))
      (node (ref "U2") (pin "15") (pinfunction "B5_15") (pintype "bidirectional"))
    )
    (net (code "80") (name "Net-(U2-B6)") (class "Default")
      (node (ref "GPIO") (pin "3") (pinfunction "3_3") (pintype "passive"))
      (node (ref "U2") (pin "14") (pinfunction "B6_14") (pintype "bidirectional"))
    )
    (net (code "81") (name "Net-(U2-B7)") (class "Default")
      (node (ref "GPIO") (pin "4") (pinfunction "4_4") (pintype "passive"))
      (node (ref "U2") (pin "13") (pinfunction "B7_13") (pintype "bidirectional"))
    )
    (net (code "82") (name "Net-(U2-B8)") (class "Default")
      (node (ref "GPIO") (pin "5") (pinfunction "5_5") (pintype "passive"))
      (node (ref "U2") (pin "12") (pinfunction "B8_12") (pintype "bidirectional"))
    )
    (net (code "83") (name "Net-(U3-INL+)") (class "Default")
      (node (ref "C1") (pin "1") (pinfunction "1_1") (pintype "passive"))
      (node (ref "U3") (pin "3") (pinfunction "INL+_3") (pintype "bidirectional"))
    )
    (net (code "84") (name "Net-(U3-INL-)") (class "Default")
      (node (ref "C3") (pin "1") (pinfunction "1_1") (pintype "passive"))
      (node (ref "U3") (pin "4") (pinfunction "INL-_4") (pintype "bidirectional"))
    )
    (net (code "85") (name "Net-(U3-INR+)") (class "Default")
      (node (ref "C2") (pin "1") (pinfunction "1_1") (pintype "passive"))
      (node (ref "U3") (pin "7") (pinfunction "INR+_7") (pintype "bidirectional"))
    )
    (net (code "86") (name "Net-(U3-INR-)") (class "Default")
      (node (ref "C4") (pin "1") (pinfunction "1_1") (pintype "passive"))
      (node (ref "U3") (pin "6") (pinfunction "INR-_6") (pintype "bidirectional"))
    )
    (net (code "87") (name "Net-(U3-OUTL+)") (class "Default")
      (node (ref "AUDIO") (pin "1") (pinfunction "1_1") (pintype "passive"))
      (node (ref "U3") (pin "13") (pinfunction "OUTL+_13") (pintype "bidirectional"))
    )
    (net (code "88") (name "Net-(U3-OUTL-)") (class "Default")
      (node (ref "AUDIO") (pin "2") (pinfunction "2_2") (pintype "passive"))
      (node (ref "U3") (pin "14") (pinfunction "OUTL-_14") (pintype "bidirectional"))
    )
    (net (code "89") (name "Net-(U3-OUTR+)") (class "Default")
      (node (ref "AUDIO") (pin "3") (pinfunction "3_3") (pintype "passive"))
      (node (ref "U3") (pin "10") (pinfunction "OUTR+_10") (pintype "bidirectional"))
    )
    (net (code "90") (name "Net-(U3-OUTR-)") (class "Default")
      (node (ref "AUDIO") (pin "4") (pinfunction "4_4") (pintype "passive"))
      (node (ref "U3") (pin "9") (pinfunction "OUTR-_9") (pintype "bidirectional"))
    )
    (net (code "91") (name "Net-(U4-AIN0)") (class "Default")
      (node (ref "A_GPIO") (pin "5") (pinfunction "5_5") (pintype "passive"))
      (node (ref "U4") (pin "4") (pinfunction "AIN0_4") (pintype "bidirectional"))
    )
    (net (code "92") (name "Net-(U4-AIN1)") (class "Default")
      (node (ref "A_GPIO") (pin "4") (pinfunction "4_4") (pintype "passive"))
      (node (ref "U4") (pin "5") (pinfunction "AIN1_5") (pintype "bidirectional"))
    )
    (net (code "93") (name "Net-(U4-AIN2)") (class "Default")
      (node (ref "A_GPIO") (pin "3") (pinfunction "3_3") (pintype "passive"))
      (node (ref "SJ2") (pin "2") (pinfunction "2_2") (pintype "passive"))
      (node (ref "U4") (pin "6") (pinfunction "AIN2_6") (pintype "bidirectional"))
    )
    (net (code "94") (name "Net-(U4-AIN3)") (class "Default")
      (node (ref "A_GPIO") (pin "2") (pinfunction "2_2") (pintype "passive"))
      (node (ref "SJ1") (pin "2") (pinfunction "2_2") (pintype "passive"))
      (node (ref "U4") (pin "7") (pinfunction "AIN3_7") (pintype "bidirectional"))
    )
    (net (code "95") (name "PEAK") (class "Default")
      (node (ref "CON1") (pin "13") (pinfunction "13_13") (pintype "passive"))
      (node (ref "IC1") (pin "7") (pinfunction "OUT_7") (pintype "output"))
      (node (ref "TP2") (pin "TP") (pinfunction "TP_TP") (pintype "input"))
    )
    (net (code "96") (name "PHOTO") (class "Default")
      (node (ref "PH1") (pin "1") (pinfunction "1_1") (pintype "passive"))
      (node (ref "R4") (pin "1") (pinfunction "1_1") (pintype "passive"))
      (node (ref "SJ2") (pin "1") (pinfunction "1_1") (pintype "passive"))
      (node (ref "U$6") (pin "1") (pinfunction "+IN_1") (pintype "bidirectional"))
    )
    (net (code "97") (name "PIR") (class "Default")
      (node (ref "CON1") (pin "23") (pinfunction "23_23") (pintype "passive"))
      (node (ref "PIR") (pin "1") (pinfunction "1_1") (pintype "passive"))
    )
    (net (code "98") (name "PWRKEY") (class "Default")
      (node (ref "CON1") (pin "9") (pinfunction "9_9") (pintype "passive"))
      (node (ref "JP1") (pin "9") (pinfunction "9_9") (pintype "passive"))
    )
    (net (code "99") (name "PWRSTAT") (class "Default")
      (node (ref "CON1") (pin "10") (pinfunction "10_10") (pintype "passive"))
      (node (ref "JP1") (pin "11") (pinfunction "11_11") (pintype "passive"))
    )
    (net (code "100") (name "Q18") (class "Default")
      (node (ref "Q2") (pin "B") (pinfunction "B_B") (pintype "passive"))
      (node (ref "Q3") (pin "3") (pinfunction "C_3") (pintype "passive"))
      (node (ref "Q4") (pin "3") (pinfunction "C_3") (pintype "passive"))
      (node (ref "R16") (pin "1") (pinfunction "1_1") (pintype "passive"))
    )
    (net (code "101") (name "RI") (class "Default")
      (node (ref "CON2") (pin "26") (pinfunction "26_26") (pintype "passive"))
      (node (ref "JP1") (pin "10") (pinfunction "10_10") (pintype "passive"))
    )
    (net (code "102") (name "RX") (class "Default")
      (node (ref "JP1") (pin "7") (pinfunction "7_7") (pintype "passive"))
      (node (ref "UEXT") (pin "4") (pinfunction "4_4") (pintype "passive"))
    )
    (net (code "103") (name "SCK") (class "Default")
      (node (ref "NRF24L01") (pin "5") (pinfunction "5_5") (pintype "passive"))
      (node (ref "U1") (pin "4") (pinfunction "SCK_4") (pintype "input"))
      (node (ref "UEXT") (pin "9") (pinfunction "9_9") (pintype "passive"))
    )
    (net (code "104") (name "SCL") (class "Default")
      (node (ref "CON1") (pin "30") (pinfunction "30_30") (pintype "passive"))
      (node (ref "U$1") (pin "P$3") (pinfunction "SCL_P$3") (pintype "bidirectional"))
      (node (ref "U$5") (pin "P$3") (pinfunction "SCL_P$3") (pintype "bidirectional"))
      (node (ref "U$6") (pin "3") (pinfunction "SCL_3") (pintype "bidirectional"))
      (node (ref "U$8") (pin "3") (pinfunction "SCL_3") (pintype "bidirectional"))
      (node (ref "U4") (pin "10") (pinfunction "SCL_10") (pintype "bidirectional"))
      (node (ref "UEXT") (pin "5") (pinfunction "5_5") (pintype "passive"))
    )
    (net (code "105") (name "SDA") (class "Default")
      (node (ref "CON1") (pin "29") (pinfunction "29_29") (pintype "passive"))
      (node (ref "U$1") (pin "P$4") (pinfunction "SDA_P$4") (pintype "bidirectional"))
      (node (ref "U$5") (pin "P$4") (pinfunction "SDA_P$4") (pintype "bidirectional"))
      (node (ref "U$6") (pin "4") (pinfunction "SDL_4") (pintype "bidirectional"))
      (node (ref "U$8") (pin "4") (pinfunction "SDL_4") (pintype "bidirectional"))
      (node (ref "U4") (pin "9") (pinfunction "SDA_9") (pintype "bidirectional"))
      (node (ref "UEXT") (pin "6") (pinfunction "6_6") (pintype "passive"))
    )
    (net (code "106") (name "TX") (class "Default")
      (node (ref "JP1") (pin "6") (pinfunction "6_6") (pintype "passive"))
      (node (ref "UEXT") (pin "3") (pinfunction "3_3") (pintype "passive"))
    )
    (net (code "107") (name "VBAT") (class "Default")
      (node (ref "BAT") (pin "1") (pinfunction "2_1") (pintype "passive"))
      (node (ref "CON1") (pin "1") (pinfunction "1_1") (pintype "passive"))
      (node (ref "SJ1") (pin "1") (pinfunction "1_1") (pintype "passive"))
      (node (ref "U$8") (pin "1") (pinfunction "+IN_1") (pintype "bidirectional"))
    )
    (net (code "108") (name "VDAC") (class "Default")
      (node (ref "CON2") (pin "6") (pinfunction "6_6") (pintype "passive"))
      (node (ref "R1") (pin "1") (pinfunction "1_1") (pintype "passive"))
    )
    (net (code "109") (name "unconnected-(CN1-PadID)") (class "Default")
      (node (ref "CN1") (pin "ID") (pinfunction "ID_ID") (pintype "bidirectional"))
    )
    (net (code "110") (name "unconnected-(CON1-Pad5)") (class "Default")
      (node (ref "CON1") (pin "5") (pinfunction "5_5") (pintype "passive"))
    )
    (net (code "111") (name "unconnected-(CON1-Pad6)") (class "Default")
      (node (ref "CON1") (pin "6") (pinfunction "6_6") (pintype "passive"))
    )
    (net (code "112") (name "unconnected-(CON1-Pad12)") (class "Default")
      (node (ref "CON1") (pin "12") (pinfunction "12_12") (pintype "passive"))
    )
    (net (code "113") (name "unconnected-(CON1-Pad27)") (class "Default")
      (node (ref "CON1") (pin "27") (pinfunction "27_27") (pintype "passive"))
    )
    (net (code "114") (name "unconnected-(CON1-Pad28)") (class "Default")
      (node (ref "CON1") (pin "28") (pinfunction "28_28") (pintype "passive"))
    )
    (net (code "115") (name "unconnected-(CON2-Pad4)") (class "Default")
      (node (ref "CON2") (pin "4") (pinfunction "4_4") (pintype "passive"))
    )
    (net (code "116") (name "unconnected-(CON2-Pad5)") (class "Default")
      (node (ref "CON2") (pin "5") (pinfunction "5_5") (pintype "passive"))
    )
    (net (code "117") (name "unconnected-(CON2-Pad7)") (class "Default")
      (node (ref "CON2") (pin "7") (pinfunction "7_7") (pintype "passive"))
    )
    (net (code "118") (name "unconnected-(CON2-Pad8)") (class "Default")
      (node (ref "CON2") (pin "8") (pinfunction "8_8") (pintype "passive"))
    )
    (net (code "119") (name "unconnected-(CON2-Pad13)") (class "Default")
      (node (ref "CON2") (pin "13") (pinfunction "13_13") (pintype "passive"))
    )
    (net (code "120") (name "unconnected-(CON2-Pad14)") (class "Default")
      (node (ref "CON2") (pin "14") (pinfunction "14_14") (pintype "passive"))
    )
    (net (code "121") (name "unconnected-(CON2-Pad21)") (class "Default")
      (node (ref "CON2") (pin "21") (pinfunction "21_21") (pintype "passive"))
    )
    (net (code "122") (name "unconnected-(CON2-Pad22)") (class "Default")
      (node (ref "CON2") (pin "22") (pinfunction "22_22") (pintype "passive"))
    )
    (net (code "123") (name "unconnected-(CON2-Pad23)") (class "Default")
      (node (ref "CON2") (pin "23") (pinfunction "23_23") (pintype "passive"))
    )
    (net (code "124") (name "unconnected-(CON2-Pad24)") (class "Default")
      (node (ref "CON2") (pin "24") (pinfunction "24_24") (pintype "passive"))
    )
    (net (code "125") (name "unconnected-(CON2-Pad25)") (class "Default")
      (node (ref "CON2") (pin "25") (pinfunction "25_25") (pintype "passive"))
    )
    (net (code "126") (name "unconnected-(IC4A-EECLK-Pad5)") (class "Default")
      (node (ref "IC4") (pin "5") (pinfunction "EECLK_5") (pintype "output"))
    )
    (net (code "127") (name "unconnected-(IC4A-{slash}OVRCUR1-Pad10)") (class "Default")
      (node (ref "IC4") (pin "10") (pinfunction "/OVRCUR1_10") (pintype "input"))
    )
    (net (code "128") (name "unconnected-(IC4A-{slash}OVRCUR2-Pad14)") (class "Default")
      (node (ref "IC4") (pin "14") (pinfunction "/OVRCUR2_14") (pintype "input"))
    )
    (net (code "129") (name "unconnected-(IC4A-{slash}OVRCUR3-Pad18)") (class "Default")
      (node (ref "IC4") (pin "18") (pinfunction "/OVRCUR3_18") (pintype "input"))
    )
    (net (code "130") (name "unconnected-(IC4A-{slash}PWRON1-Pad9)") (class "Default")
      (node (ref "IC4") (pin "9") (pinfunction "/PWRON1_9") (pintype "output"))
    )
    (net (code "131") (name "unconnected-(IC4A-{slash}PWRON2-Pad13)") (class "Default")
      (node (ref "IC4") (pin "13") (pinfunction "/PWRON2_13") (pintype "output"))
    )
    (net (code "132") (name "unconnected-(IC4A-{slash}PWRON3-Pad17)") (class "Default")
      (node (ref "IC4") (pin "17") (pinfunction "/PWRON3_17") (pintype "output"))
    )
    (net (code "133") (name "unconnected-(JP1-Pad2)") (class "Default")
      (node (ref "JP1") (pin "2") (pinfunction "2_2") (pintype "passive"))
    )
    (net (code "134") (name "unconnected-(JP1-Pad5)") (class "Default")
      (node (ref "JP1") (pin "5") (pinfunction "5_5") (pintype "passive"))
    )
    (net (code "135") (name "unconnected-(JP1-Pad8)") (class "Default")
      (node (ref "JP1") (pin "8") (pinfunction "8_8") (pintype "passive"))
    )
    (net (code "136") (name "unconnected-(JP1-Pad13)") (class "Default")
      (node (ref "JP1") (pin "13") (pinfunction "13_13") (pintype "passive"))
    )
    (net (code "137") (name "unconnected-(JP1-Pad14)") (class "Default")
      (node (ref "JP1") (pin "14") (pinfunction "14_14") (pintype "passive"))
    )
    (net (code "138") (name "unconnected-(U1-DIO0-Pad14)") (class "Default")
      (node (ref "U1") (pin "14") (pinfunction "DIO0_14") (pintype "bidirectional"))
    )
    (net (code "139") (name "unconnected-(U1-DIO1-Pad15)") (class "Default")
      (node (ref "U1") (pin "15") (pinfunction "DIO1_15") (pintype "bidirectional"))
    )
    (net (code "140") (name "unconnected-(U2-A1-Pad1)") (class "Default")
      (node (ref "U2") (pin "1") (pinfunction "A1_1") (pintype "bidirectional"))
    )
    (net (code "141") (name "unconnected-(U2-A2-Pad3)") (class "Default")
      (node (ref "U2") (pin "3") (pinfunction "A2_3") (pintype "bidirectional"))
    )
    (net (code "142") (name "unconnected-(U2-A3-Pad4)") (class "Default")
      (node (ref "U2") (pin "4") (pinfunction "A3_4") (pintype "bidirectional"))
    )
    (net (code "143") (name "unconnected-(U2-B1-Pad20)") (class "Default")
      (node (ref "U2") (pin "20") (pinfunction "B1_20") (pintype "bidirectional"))
    )
    (net (code "144") (name "unconnected-(U2-B2-Pad18)") (class "Default")
      (node (ref "U2") (pin "18") (pinfunction "B2_18") (pintype "bidirectional"))
    )
    (net (code "145") (name "unconnected-(U2-B3-Pad17)") (class "Default")
      (node (ref "U2") (pin "17") (pinfunction "B3_17") (pintype "bidirectional"))
    )
    (net (code "146") (name "unconnected-(U2-OE-Pad10)") (class "Default")
      (node (ref "U2") (pin "10") (pinfunction "OE_10") (pintype "bidirectional"))
    )
    (net (code "147") (name "unconnected-(U4-ADDR-Pad1)") (class "Default")
      (node (ref "U4") (pin "1") (pinfunction "ADDR_1") (pintype "bidirectional"))
    )
    (net (code "148") (name "unconnected-(U4-ALERT{slash}RDY-Pad2)") (class "Default")
      (node (ref "U4") (pin "2") (pinfunction "ALERT/RDY_2") (pintype "bidirectional"))
    )
  )
)
